# solenoid_1ch.net
KiCad netlist of a schematic drawn in EAGLE
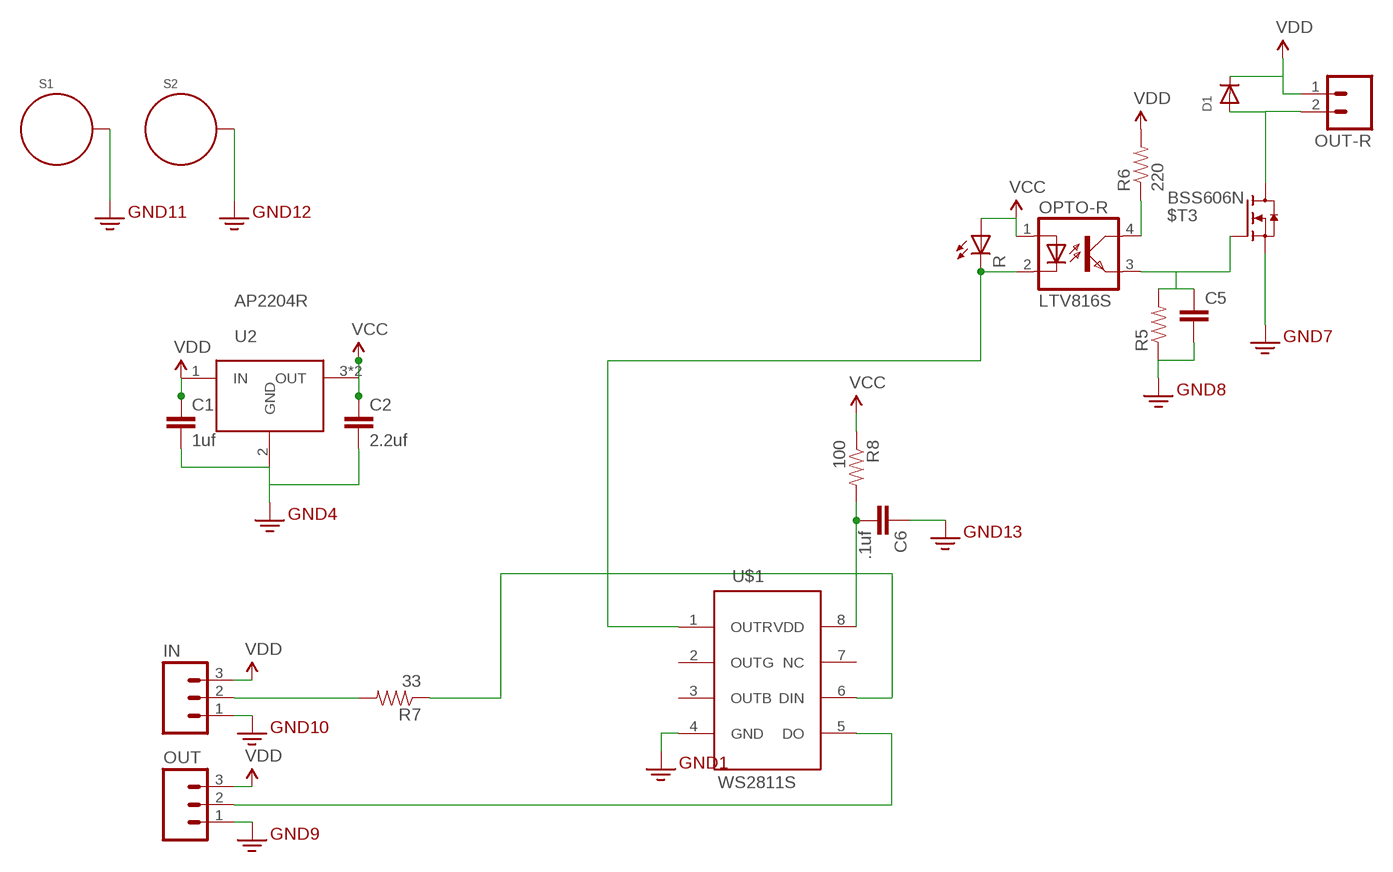
[diagram p0: schematic, sheet 1]

(export (version "E")
  (design (tool "Eeschema 10.0.6"))
  (components
    (comp (ref "$T3")
      (value "BSS606N")
      (footprint "eagle-import:SOT89R")
      (libsource (lib "eagle-import") (part "BSS606N"))
    )
    (comp (ref "C1")
      (value "1uf")
      (footprint "eagle-import:0805")
      (libsource (lib "eagle-import") (part "CAP0805"))
    )
    (comp (ref "C2")
      (value "2.2uf")
      (footprint "eagle-import:0805")
      (libsource (lib "eagle-import") (part "CAP0805"))
    )
    (comp (ref "C5")
      (value "CAP0805")
      (footprint "eagle-import:0805")
      (libsource (lib "eagle-import") (part "CAP0805"))
    )
    (comp (ref "C6")
      (value ".1uf")
      (footprint "eagle-import:0805")
      (libsource (lib "eagle-import") (part "CAP0805"))
    )
    (comp (ref "D1")
      (value "DIODESOD-123")
      (footprint "eagle-import:SOD-123")
      (libsource (lib "eagle-import") (part "DIODESOD-123"))
    )
    (comp (ref "IN")
      (value "M031X03_NO_SILK")
      (footprint "eagle-import:1X03_NO_SILK")
      (libsource (lib "eagle-import") (part "M031X03_NO_SILK"))
    )
    (comp (ref "OPTO-R")
      (value "LTV816S")
      (footprint "eagle-import:SMD4")
      (libsource (lib "eagle-import") (part "LTV816S"))
    )
    (comp (ref "OUT")
      (value "M031X03_NO_SILK")
      (footprint "eagle-import:1X03_NO_SILK")
      (libsource (lib "eagle-import") (part "M031X03_NO_SILK"))
    )
    (comp (ref "OUT-R")
      (value "M02PTH")
      (footprint "eagle-import:1X02")
      (libsource (lib "eagle-import") (part "M02PTH"))
    )
    (comp (ref "R")
      (value "LEDCHIPLED_0805")
      (footprint "eagle-import:CHIPLED_0805")
      (libsource (lib "eagle-import") (part "LEDCHIPLED_0805"))
    )
    (comp (ref "R5")
      (value "RESISTOR0805-RES")
      (footprint "eagle-import:0805")
      (libsource (lib "eagle-import") (part "RESISTOR0805-RES"))
    )
    (comp (ref "R6")
      (value "220")
      (footprint "eagle-import:0805")
      (libsource (lib "eagle-import") (part "RESISTOR0805-RES"))
    )
    (comp (ref "R7")
      (value "33")
      (footprint "eagle-import:0805")
      (libsource (lib "eagle-import") (part "RESISTOR0805-RES"))
    )
    (comp (ref "R8")
      (value "100")
      (footprint "eagle-import:0805")
      (libsource (lib "eagle-import") (part "RESISTOR0805-RES"))
    )
    (comp (ref "S1")
      (value "STANDOFF_ELECTRICAL")
      (footprint "eagle-import:STANDOFF-ELECTRICAL")
      (libsource (lib "eagle-import") (part "STANDOFF_ELECTRICAL"))
    )
    (comp (ref "S2")
      (value "STANDOFF_ELECTRICAL")
      (footprint "eagle-import:STANDOFF-ELECTRICAL")
      (libsource (lib "eagle-import") (part "STANDOFF_ELECTRICAL"))
    )
    (comp (ref "U$1")
      (value "WS2811S")
      (footprint "eagle-import:MSOP8")
      (libsource (lib "eagle-import") (part "WS2811S"))
    )
    (comp (ref "U2")
      (value "AP2204R")
      (footprint "eagle-import:SOT89R")
      (fields (field (name "VOLTAGE") "5.0"))
      (libsource (lib "eagle-import") (part "AP2204R"))
    )
  )
  (nets
    (net (code "1") (name "GND2") (class "Default")
      (node (ref "$T3") (pin "1") (pinfunction "S_1") (pintype "passive"))
      (node (ref "C1") (pin "2") (pinfunction "2_2") (pintype "passive"))
      (node (ref "C2") (pin "2") (pinfunction "2_2") (pintype "passive"))
      (node (ref "C5") (pin "2") (pinfunction "2_2") (pintype "passive"))
      (node (ref "C6") (pin "1") (pinfunction "1_1") (pintype "passive"))
      (node (ref "IN") (pin "1") (pinfunction "1_1") (pintype "passive"))
      (node (ref "OUT") (pin "1") (pinfunction "1_1") (pintype "passive"))
      (node (ref "R5") (pin "1") (pinfunction "1_1") (pintype "passive"))
      (node (ref "S1") (pin "P1") (pinfunction "P$1_P1") (pintype "bidirectional"))
      (node (ref "S2") (pin "P1") (pinfunction "P$1_P1") (pintype "bidirectional"))
      (node (ref "U$1") (pin "4") (pinfunction "GND_4") (pintype "power_in"))
      (node (ref "U2") (pin "2") (pinfunction "GND_2") (pintype "power_in"))
    )
    (net (code "2") (name "Net-($T3-D-Pad3)") (class "Default")
      (node (ref "$T3") (pin "3") (pinfunction "D_3") (pintype "passive"))
      (node (ref "$T3") (pin "4") (pinfunction "D_4") (pintype "passive"))
      (node (ref "D1") (pin "A") (pinfunction "A_A") (pintype "passive"))
      (node (ref "OUT-R") (pin "2") (pinfunction "2_2") (pintype "passive"))
    )
    (net (code "3") (name "Net-($T3-G)") (class "Default")
      (node (ref "$T3") (pin "2") (pinfunction "G_2") (pintype "passive"))
      (node (ref "C5") (pin "1") (pinfunction "1_1") (pintype "passive"))
      (node (ref "OPTO-R") (pin "3") (pinfunction "EMIT_3") (pintype "passive"))
      (node (ref "R5") (pin "2") (pinfunction "2_2") (pintype "passive"))
    )
    (net (code "4") (name "Net-(IN-Pad2)") (class "Default")
      (node (ref "IN") (pin "2") (pinfunction "2_2") (pintype "passive"))
      (node (ref "R7") (pin "2") (pinfunction "2_2") (pintype "passive"))
    )
    (net (code "5") (name "Net-(OPTO-R-C)") (class "Default")
      (node (ref "OPTO-R") (pin "2") (pinfunction "C_2") (pintype "passive"))
      (node (ref "R") (pin "C") (pinfunction "C_C") (pintype "passive"))
      (node (ref "U$1") (pin "1") (pinfunction "OUTR_1") (pintype "output"))
    )
    (net (code "6") (name "Net-(OPTO-R-COL)") (class "Default")
      (node (ref "OPTO-R") (pin "4") (pinfunction "COL_4") (pintype "passive"))
      (node (ref "R6") (pin "1") (pinfunction "1_1") (pintype "passive"))
    )
    (net (code "7") (name "Net-(U$1-DIN)") (class "Default")
      (node (ref "R7") (pin "1") (pinfunction "1_1") (pintype "passive"))
      (node (ref "U$1") (pin "6") (pinfunction "DIN_6") (pintype "input"))
    )
    (net (code "8") (name "Net-(U$1-DO)") (class "Default")
      (node (ref "OUT") (pin "2") (pinfunction "2_2") (pintype "passive"))
      (node (ref "U$1") (pin "5") (pinfunction "DO_5") (pintype "output"))
    )
    (net (code "9") (name "Net-(U$1-VDD)") (class "Default")
      (node (ref "C6") (pin "2") (pinfunction "2_2") (pintype "passive"))
      (node (ref "R8") (pin "2") (pinfunction "2_2") (pintype "passive"))
      (node (ref "U$1") (pin "8") (pinfunction "VDD_8") (pintype "power_in"))
    )
    (net (code "10") (name "VCC") (class "Default")
      (node (ref "C2") (pin "1") (pinfunction "1_1") (pintype "passive"))
      (node (ref "OPTO-R") (pin "1") (pinfunction "A_1") (pintype "passive"))
      (node (ref "R") (pin "A") (pinfunction "A_A") (pintype "passive"))
      (node (ref "R8") (pin "1") (pinfunction "1_1") (pintype "passive"))
      (node (ref "U2") (pin "3") (pinfunction "OUT_3") (pintype "power_in"))
      (node (ref "U2") (pin "4") (pinfunction "OUT_4") (pintype "power_in"))
    )
    (net (code "11") (name "VDD") (class "Default")
      (node (ref "C1") (pin "1") (pinfunction "1_1") (pintype "passive"))
      (node (ref "D1") (pin "C") (pinfunction "C_C") (pintype "passive"))
      (node (ref "IN") (pin "3") (pinfunction "3_3") (pintype "passive"))
      (node (ref "OUT") (pin "3") (pinfunction "3_3") (pintype "passive"))
      (node (ref "OUT-R") (pin "1") (pinfunction "1_1") (pintype "passive"))
      (node (ref "R6") (pin "2") (pinfunction "2_2") (pintype "passive"))
      (node (ref "U2") (pin "1") (pinfunction "IN_1") (pintype "power_in"))
    )
    (net (code "12") (name "unconnected-(U$1-NC-Pad7)") (class "Default")
      (node (ref "U$1") (pin "7") (pinfunction "NC_7") (pintype "no_connect"))
    )
    (net (code "13") (name "unconnected-(U$1-OUTB-Pad3)") (class "Default")
      (node (ref "U$1") (pin "3") (pinfunction "OUTB_3") (pintype "output"))
    )
    (net (code "14") (name "unconnected-(U$1-OUTG-Pad2)") (class "Default")
      (node (ref "U$1") (pin "2") (pinfunction "OUTG_2") (pintype "output"))
    )
  )
)
